# SSTuino_II.net
KiCad netlist of a schematic drawn in EAGLE
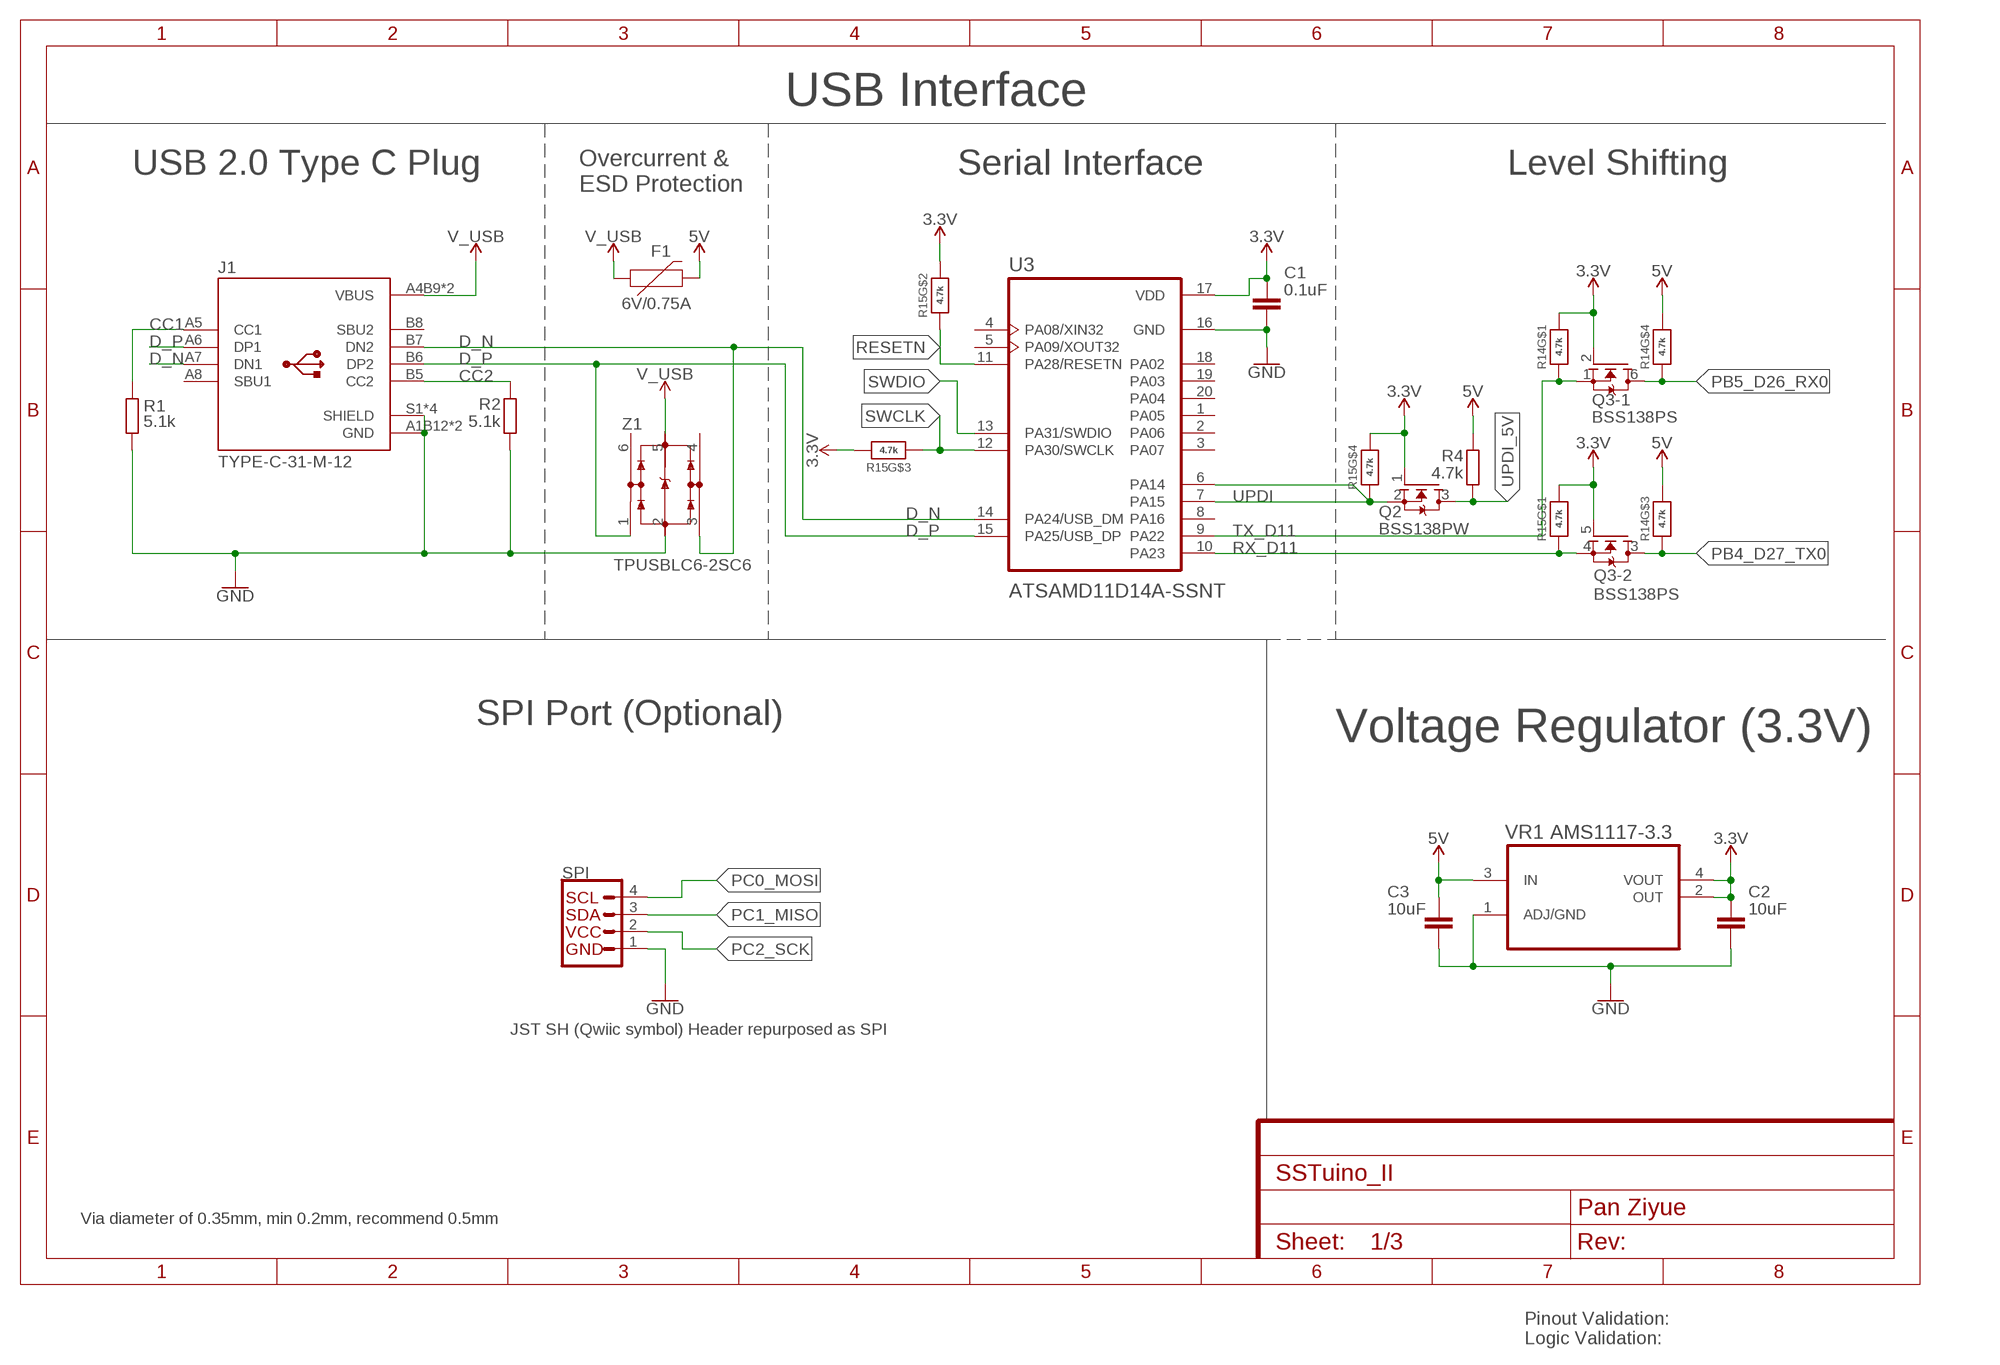
[diagram p0: schematic, sheet 1]
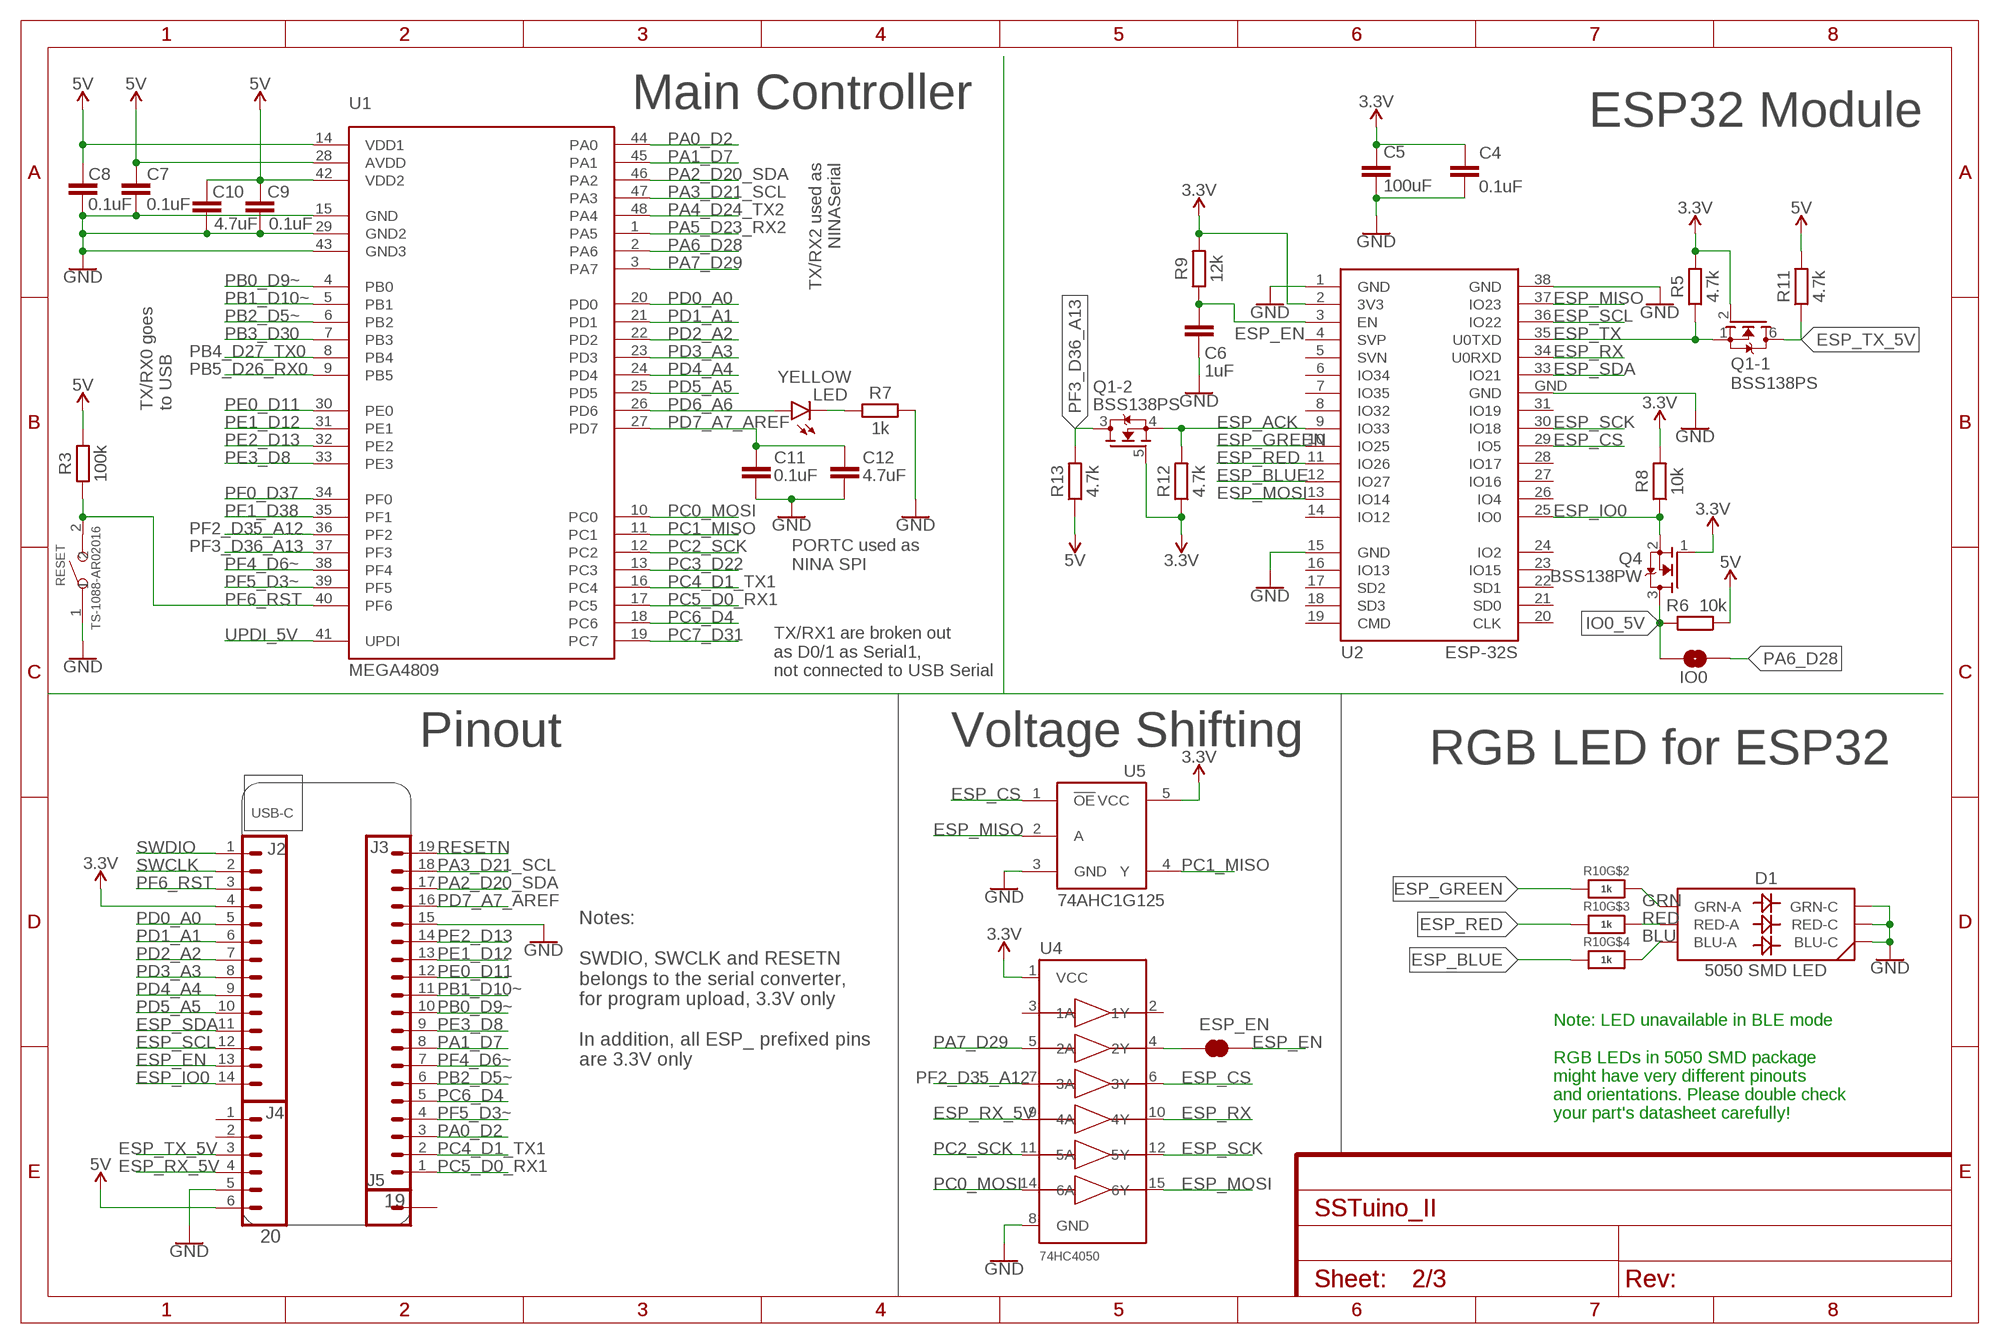
[diagram p1: schematic, sheet 2]
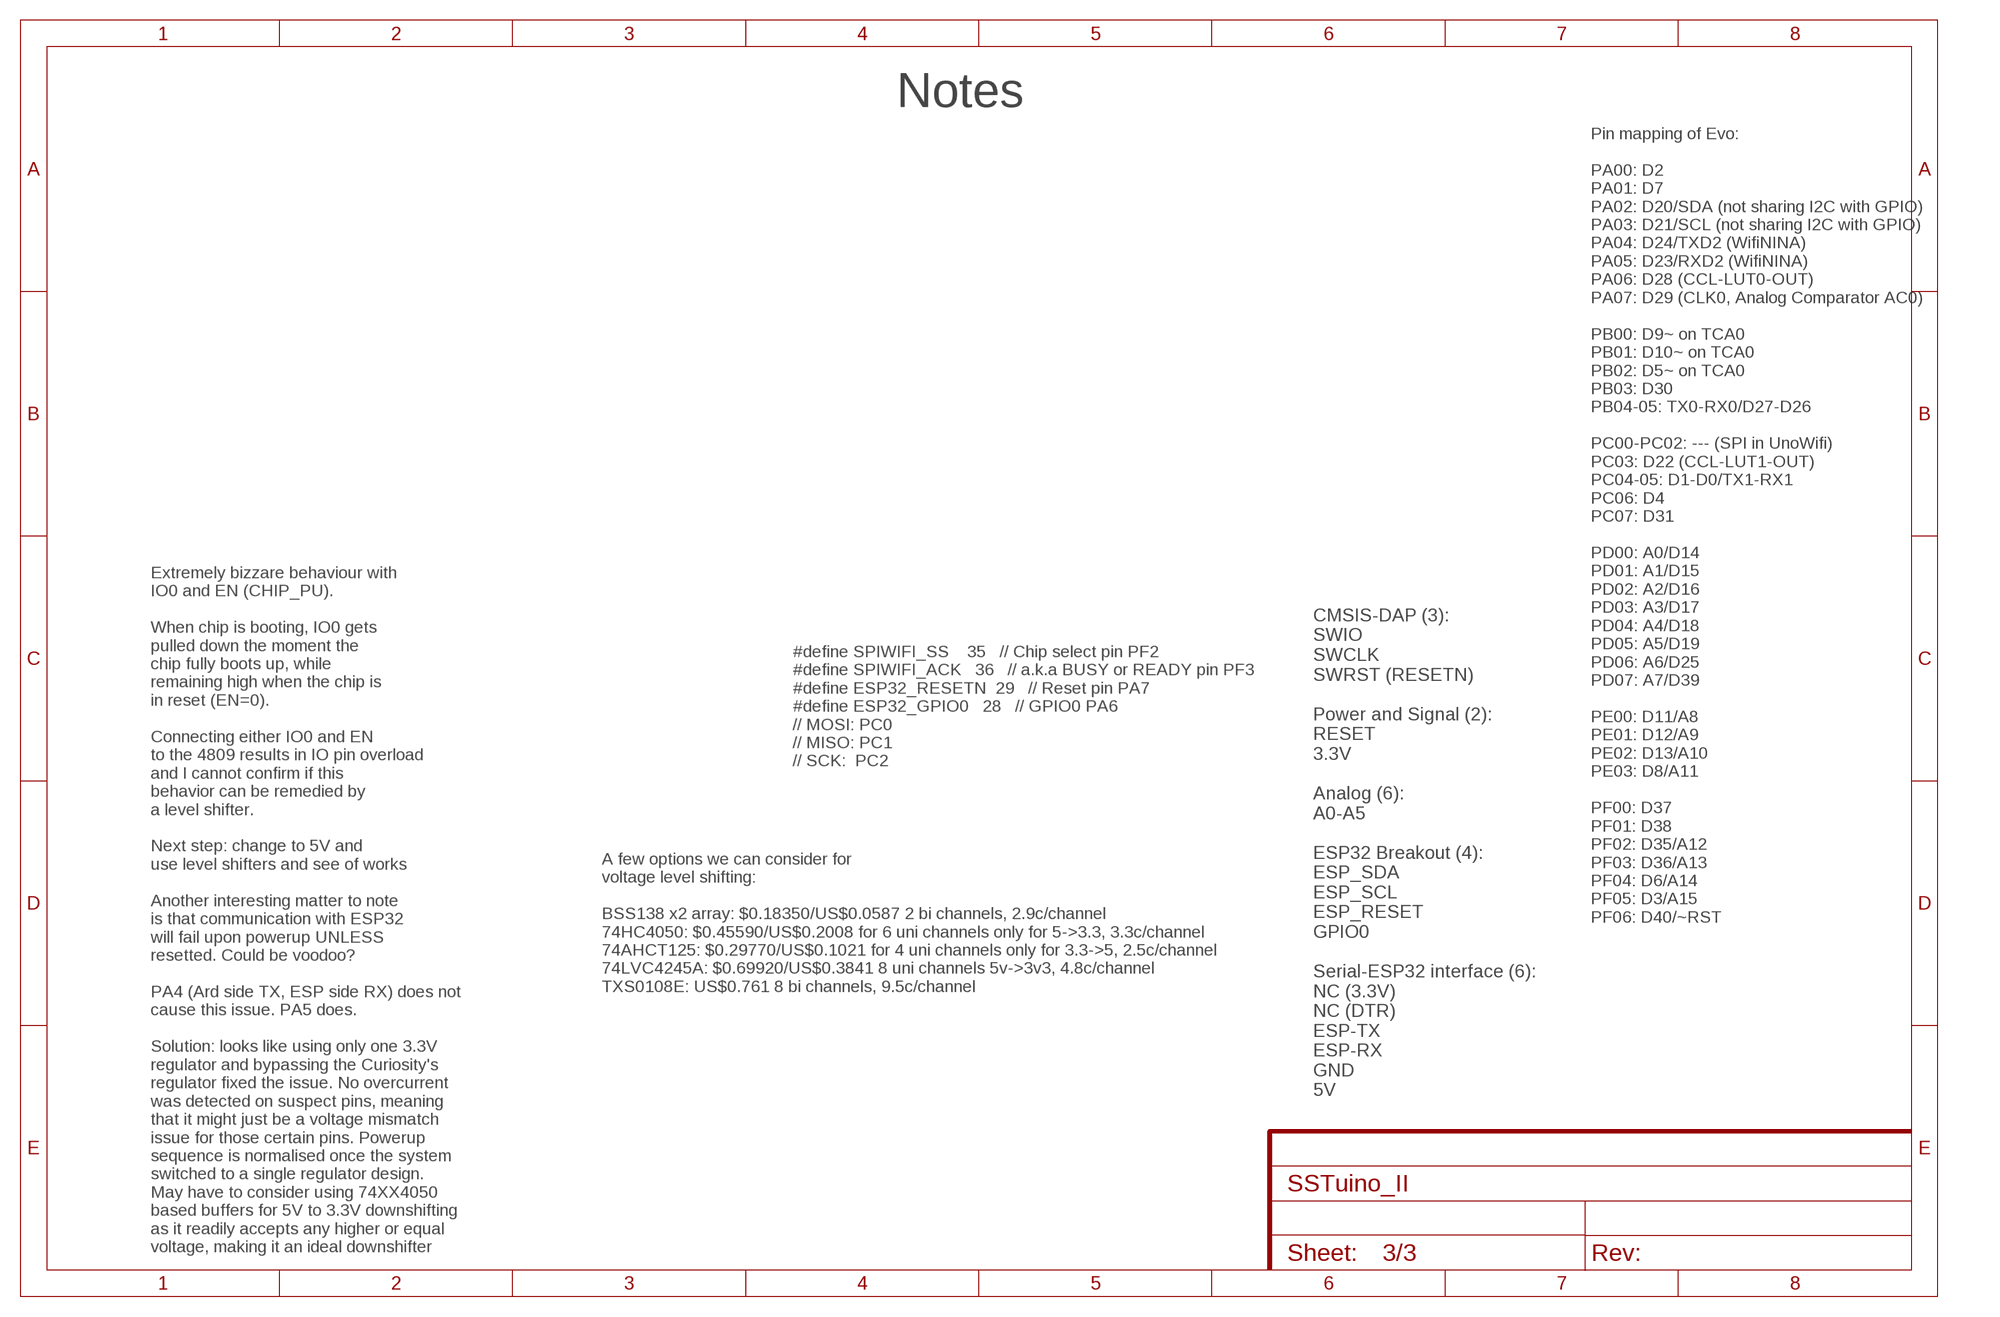
[diagram p2: schematic, sheet 3]

(export (version "E")
  (design (tool "Eeschema 10.0.6"))
  (components
    (comp (ref "C4")
      (value "0.1uF")
      (footprint "eagle-import:CAPC1005X60")
      (fields (field (name "LCSC_PART") "C1525"))
      (libsource (lib "eagle-import") (part "CCHIP-0402(1005-METRIC)_"))
    )
    (comp (ref "C5")
      (value "100uF")
      (footprint "eagle-import:CAPC3216X135")
      (fields (field (name "LCSC_PART") "C15008"))
      (libsource (lib "eagle-import") (part "CCHIP-1206(3216-METRIC)_"))
    )
    (comp (ref "C6")
      (value "1uF")
      (footprint "eagle-import:CAPC1005X60")
      (fields (field (name "LCSC_PART") "C52923"))
      (libsource (lib "eagle-import") (part "CCHIP-0402(1005-METRIC)_"))
    )
    (comp (ref "C7")
      (value "0.1uF")
      (footprint "eagle-import:CAPC1005X60")
      (libsource (lib "eagle-import") (part "CCHIP-0402(1005-METRIC)_"))
    )
    (comp (ref "C8")
      (value "0.1uF")
      (footprint "eagle-import:CAPC1005X60")
      (libsource (lib "eagle-import") (part "CCHIP-0402(1005-METRIC)_"))
    )
    (comp (ref "C9")
      (value "0.1uF")
      (footprint "eagle-import:CAPC1005X60")
      (libsource (lib "eagle-import") (part "CCHIP-0402(1005-METRIC)_"))
    )
    (comp (ref "C10")
      (value "4.7uF")
      (footprint "eagle-import:CAPC1005X60")
      (libsource (lib "eagle-import") (part "CCHIP-0402(1005-METRIC)_"))
    )
    (comp (ref "C11")
      (value "0.1uF")
      (footprint "eagle-import:CAPC1005X60")
      (fields (field (name "LCSC_PART") "C1525"))
      (libsource (lib "eagle-import") (part "CCHIP-0402(1005-METRIC)_"))
    )
    (comp (ref "C12")
      (value "4.7uF")
      (footprint "eagle-import:CAPC1005X60")
      (fields (field (name "LCSC_PART") "C23733"))
      (libsource (lib "eagle-import") (part "CCHIP-0402(1005-METRIC)_"))
    )
    (comp (ref "D1")
      (value "5050 SMD LED")
      (footprint "eagle-import:LED-TRICOLOR-5050")
      (fields (field (name "LCSC_PART") "C784540"))
      (libsource (lib "eagle-import") (part "LED-RGBTC5050RGBF08"))
    )
    (comp (ref "ESP_EN")
      (value "JUMPER-SMT_2_NC_TRACE_SILK")
      (footprint "eagle-import:SMT-JUMPER_2_NC_TRACE_SILK")
      (libsource (lib "eagle-import") (part "JUMPER-SMT_2_NC_TRACE_SILK"))
    )
    (comp (ref "IO0")
      (value "JUMPER-SMT_2_NO_SILK")
      (footprint "eagle-import:SMT-JUMPER_2_NO_SILK")
      (libsource (lib "eagle-import") (part "JUMPER-SMT_2_NO_SILK"))
    )
    (comp (ref "J2")
      (value "CONN_14NO_SILK")
      (footprint "eagle-import:1X14_NO_SILK")
      (libsource (lib "eagle-import") (part "CONN_14NO_SILK"))
    )
    (comp (ref "J3")
      (value "CONN_191X19_NO_SILK")
      (footprint "eagle-import:1X19_NO_SILK")
      (libsource (lib "eagle-import") (part "CONN_191X19_NO_SILK"))
    )
    (comp (ref "J4")
      (value "CONN_06NO_SILK_FEMALE_PTH")
      (footprint "eagle-import:1X06_NO_SILK")
      (libsource (lib "eagle-import") (part "CONN_06NO_SILK_FEMALE_PTH"))
    )
    (comp (ref "J5")
      (value "CONN_01PTH_NO_SILK_YES_STOP")
      (footprint "eagle-import:1X01_NO_SILK")
      (libsource (lib "eagle-import") (part "CONN_01PTH_NO_SILK_YES_STOP"))
    )
    (comp (ref "LED")
      (value "YELLOW")
      (footprint "eagle-import:LED-0603")
      (fields (field (name "LCSC_PART") "C72038"))
      (libsource (lib "eagle-import") (part "LED0603"))
    )
    (comp (ref "Q1")
      (value "BSS138PS")
      (footprint "eagle-import:ARDUINO-TRANSISTORS_SOT363")
      (fields (field (name "MANUFACTURER") "NXP") (field (name "LCSC_PART") "C193381"))
      (libsource (lib "eagle-import") (part "BSS138PS"))
    )
    (comp (ref "Q4")
      (value "BSS138PW")
      (footprint "eagle-import:SOT65P210X110-3N")
      (fields (field (name "MF") "NXP Semiconductors") (field (name "LCSC_PART") "C919583"))
      (libsource (lib "eagle-import") (part "BSS138PW"))
    )
    (comp (ref "R3")
      (value "100k")
      (footprint "eagle-import:RESC1005X40")
      (fields (field (name "LCSC_PART") "C25741"))
      (libsource (lib "eagle-import") (part "RCHIP-0402(1005-METRIC)_"))
    )
    (comp (ref "R5")
      (value "4.7k")
      (footprint "eagle-import:RESC1005X40")
      (fields (field (name "LCSC_PART") "C25900"))
      (libsource (lib "eagle-import") (part "RCHIP-0402(1005-METRIC)_"))
    )
    (comp (ref "R6")
      (value "10k")
      (footprint "eagle-import:RESC1005X40")
      (fields (field (name "LCSC_PART") "C25744"))
      (libsource (lib "eagle-import") (part "RCHIP-0402(1005-METRIC)_"))
    )
    (comp (ref "R7")
      (value "1k")
      (footprint "eagle-import:RESC1005X40")
      (fields (field (name "LCSC_PART") "C11702"))
      (libsource (lib "eagle-import") (part "RCHIP-0402(1005-METRIC)_"))
    )
    (comp (ref "R8")
      (value "10k")
      (footprint "eagle-import:RESC1005X40")
      (fields (field (name "LCSC_PART") "C25744"))
      (libsource (lib "eagle-import") (part "RCHIP-0402(1005-METRIC)_"))
    )
    (comp (ref "R9")
      (value "12k")
      (footprint "eagle-import:RESC1005X40")
      (fields (field (name "LCSC_PART") "C25752"))
      (libsource (lib "eagle-import") (part "RCHIP-0402(1005-METRIC)_"))
    )
    (comp (ref "R10")
      (value "1k")
      (footprint "eagle-import:RESPACK_4X0402")
      (fields (field (name "LCSC_PART") "C25726"))
      (libsource (lib "eagle-import") (part "RESISTOR_4PACK0402"))
    )
    (comp (ref "R11")
      (value "4.7k")
      (footprint "eagle-import:RESC1005X40")
      (fields (field (name "LCSC_PART") "C25900"))
      (libsource (lib "eagle-import") (part "RCHIP-0402(1005-METRIC)_"))
    )
    (comp (ref "R12")
      (value "4.7k")
      (footprint "eagle-import:RESC1005X40")
      (fields (field (name "LCSC_PART") "C25900"))
      (libsource (lib "eagle-import") (part "RCHIP-0402(1005-METRIC)_"))
    )
    (comp (ref "R13")
      (value "4.7k")
      (footprint "eagle-import:RESC1005X40")
      (fields (field (name "LCSC_PART") "C25900"))
      (libsource (lib "eagle-import") (part "RCHIP-0402(1005-METRIC)_"))
    )
    (comp (ref "RESET")
      (value "TS-1088-AR02016")
      (footprint "eagle-import:SW2-2.6-3.9X2.9X1.5+0.4MM")
      (fields
        (field (name "LCSC_PART") "C115357")
        (field (name "MPN") "SKRKAEE020")
        (field (name "LCSC_PART_1") "C720477")
      )
      (libsource (lib "eagle-import") (part "SMD-BUTTON(2P-3.9X2.9X1.5+0.4MM)-SKRKAEE020"))
    )
    (comp (ref "U1")
      (value "MEGA4809")
      (footprint "eagle-import:TQFP48")
      (fields (field (name "LCSC_PART") "C189475"))
      (libsource (lib "eagle-import") (part "MEGA4809"))
    )
    (comp (ref "U2")
      (value "ESP-32S")
      (footprint "eagle-import:ESP-32S")
      (fields (field (name "LCSC_PART") "C277944"))
      (libsource (lib "eagle-import") (part "ESP-32S"))
    )
    (comp (ref "U4")
      (value "74HC4050")
      (footprint "eagle-import:TSSOP16")
      (fields (field (name "LCSC_PART") "C352825"))
      (libsource (lib "eagle-import") (part "74HC4050DTSSOP"))
    )
    (comp (ref "U5")
      (value "74AHC1G125")
      (footprint "eagle-import:SOT23-5L")
      (fields (field (name "LCSC_PART") "C7468"))
      (libsource (lib "eagle-import") (part "74AHC1G125"))
    )
    (comp (ref "C1")
      (value "0.1uF")
      (footprint "eagle-import:CAPC1005X60")
      (fields (field (name "LCSC_PART") "C696352"))
      (libsource (lib "eagle-import") (part "CCHIP-0402(1005-METRIC)_"))
    )
    (comp (ref "C2")
      (value "10uF")
      (footprint "eagle-import:CAPC1608X85")
      (fields (field (name "LCSC_PART") "C19702"))
      (libsource (lib "eagle-import") (part "CCHIP-0603(1608-METRIC)_"))
    )
    (comp (ref "C3")
      (value "10uF")
      (footprint "eagle-import:CAPC1608X85")
      (fields (field (name "LCSC_PART") "C19702"))
      (libsource (lib "eagle-import") (part "CCHIP-0603(1608-METRIC)_"))
    )
    (comp (ref "F1")
      (value "6V/0.75A")
      (footprint "eagle-import:1206")
      (fields (field (name "LCSC_PART") "C99563"))
      (libsource (lib "eagle-import") (part "PPTC_THREE-QUARTER-AMP"))
    )
    (comp (ref "J1")
      (value "TYPE-C-31-M-12")
      (footprint "eagle-import:HRO_TYPE-C-31-M-12")
      (fields (field (name "MF") "HRO Electronics Co., Ltd.") (field (name "LCSC_PART") "C165948"))
      (libsource (lib "eagle-import") (part "TYPE-C-31-M-12"))
    )
    (comp (ref "Q2")
      (value "BSS138PW")
      (footprint "eagle-import:SOT65P210X110-3N")
      (fields (field (name "MF") "NXP Semiconductors") (field (name "LCSC_PART") "C193366"))
      (libsource (lib "eagle-import") (part "BSS138PW"))
    )
    (comp (ref "Q3")
      (value "BSS138PS")
      (footprint "eagle-import:ARDUINO-TRANSISTORS_SOT363")
      (fields (field (name "MANUFACTURER") "NXP") (field (name "LCSC_PART") "C193381"))
      (libsource (lib "eagle-import") (part "BSS138PS"))
    )
    (comp (ref "R1")
      (value "5.1k")
      (footprint "eagle-import:RESC1005X40")
      (fields (field (name "LCSC_PART") "C25905"))
      (libsource (lib "eagle-import") (part "RCHIP-0402(1005-METRIC)_"))
    )
    (comp (ref "R2")
      (value "5.1k")
      (footprint "eagle-import:RESC1005X40")
      (fields (field (name "LCSC_PART") "C25905"))
      (libsource (lib "eagle-import") (part "RCHIP-0402(1005-METRIC)_"))
    )
    (comp (ref "R4")
      (value "4.7k")
      (footprint "eagle-import:RESC1005X40")
      (fields (field (name "LCSC_PART") "C25900"))
      (libsource (lib "eagle-import") (part "RCHIP-0402(1005-METRIC)_"))
    )
    (comp (ref "R14")
      (value "4.7k")
      (footprint "eagle-import:RESPACK_4X0402")
      (fields (field (name "LCSC_PART") "C29586"))
      (libsource (lib "eagle-import") (part "RESISTOR_4PACK0402"))
    )
    (comp (ref "R15")
      (value "4.7k")
      (footprint "eagle-import:RESPACK_4X0402")
      (fields (field (name "LCSC_PART") "C29586"))
      (libsource (lib "eagle-import") (part "RESISTOR_4PACK0402"))
    )
    (comp (ref "SPI")
      (value "QWIIC_CONNECTORJS-1MM")
      (footprint "eagle-import:1X04_1MM_RA")
      (libsource (lib "eagle-import") (part "QWIIC_CONNECTORJS-1MM"))
    )
    (comp (ref "U3")
      (value "ATSAMD11D14A-SSNT")
      (footprint "eagle-import:SOIC127P1030X265-20N")
      (fields (field (name "MF") "Microchip") (field (name "LCSC_PART") "C2053599"))
      (libsource (lib "eagle-import") (part "ATSAMD11D14A-SSNT"))
    )
    (comp (ref "VR1")
      (value "AMS1117-3.3")
      (footprint "eagle-import:SOT230P696X180-4N")
      (fields (field (name "MPN") "LM1117MP-3.3") (field (name "LCSC_PART") "C6186"))
      (libsource (lib "eagle-import") (part "LM1117MP-3.3"))
    )
    (comp (ref "Z1")
      (value "TPUSBLC6-2SC6")
      (footprint "eagle-import:SOT95P280X110-6N")
      (fields (field (name "LCSC_PART") "C558442"))
      (libsource (lib "eagle-import") (part "TPUSBLC6-2SC6"))
    )
  )
  (nets
    (net (code "1") (name "3.3V") (class "Default")
      (node (ref "C1") (pin "1") (pinfunction "1_1") (pintype "passive"))
      (node (ref "C2") (pin "1") (pinfunction "1_1") (pintype "passive"))
      (node (ref "C4") (pin "1") (pinfunction "1_1") (pintype "passive"))
      (node (ref "C5") (pin "1") (pinfunction "1_1") (pintype "passive"))
      (node (ref "J2") (pin "4") (pinfunction "4_4") (pintype "passive"))
      (node (ref "Q1") (pin "2") (pinfunction "G_2") (pintype "passive"))
      (node (ref "Q1") (pin "5") (pinfunction "G_5") (pintype "passive"))
      (node (ref "Q2") (pin "1") (pinfunction "G_1") (pintype "passive"))
      (node (ref "Q3") (pin "2") (pinfunction "G_2") (pintype "passive"))
      (node (ref "Q3") (pin "5") (pinfunction "G_5") (pintype "passive"))
      (node (ref "Q4") (pin "1") (pinfunction "G_1") (pintype "passive"))
      (node (ref "R12") (pin "1") (pinfunction "1_1") (pintype "passive"))
      (node (ref "R14") (pin "8") (pinfunction "2_8") (pintype "passive"))
      (node (ref "R15") (pin "5") (pinfunction "2_5") (pintype "passive"))
      (node (ref "R15") (pin "6") (pinfunction "2_6") (pintype "passive"))
      (node (ref "R15") (pin "7") (pinfunction "2_7") (pintype "passive"))
      (node (ref "R15") (pin "8") (pinfunction "2_8") (pintype "passive"))
      (node (ref "R5") (pin "2") (pinfunction "2_2") (pintype "passive"))
      (node (ref "R8") (pin "2") (pinfunction "2_2") (pintype "passive"))
      (node (ref "R9") (pin "2") (pinfunction "2_2") (pintype "passive"))
      (node (ref "U2") (pin "2") (pinfunction "3V3_2") (pintype "power_in"))
      (node (ref "U3") (pin "17") (pinfunction "VDD_17") (pintype "power_in"))
      (node (ref "U4") (pin "1") (pinfunction "VCC_1") (pintype "bidirectional"))
      (node (ref "U5") (pin "5") (pinfunction "VCC_5") (pintype "power_in"))
      (node (ref "VR1") (pin "2") (pinfunction "OUT_2") (pintype "output"))
      (node (ref "VR1") (pin "4") (pinfunction "VOUT_4") (pintype "output"))
    )
    (net (code "2") (name "5V") (class "Default")
      (node (ref "C10") (pin "1") (pinfunction "1_1") (pintype "passive"))
      (node (ref "C3") (pin "1") (pinfunction "1_1") (pintype "passive"))
      (node (ref "C7") (pin "1") (pinfunction "1_1") (pintype "passive"))
      (node (ref "C8") (pin "1") (pinfunction "1_1") (pintype "passive"))
      (node (ref "C9") (pin "1") (pinfunction "1_1") (pintype "passive"))
      (node (ref "F1") (pin "2") (pinfunction "2_2") (pintype "bidirectional"))
      (node (ref "J4") (pin "6") (pinfunction "6_6") (pintype "passive"))
      (node (ref "R11") (pin "2") (pinfunction "2_2") (pintype "passive"))
      (node (ref "R13") (pin "1") (pinfunction "1_1") (pintype "passive"))
      (node (ref "R14") (pin "5") (pinfunction "2_5") (pintype "passive"))
      (node (ref "R14") (pin "6") (pinfunction "2_6") (pintype "passive"))
      (node (ref "R3") (pin "2") (pinfunction "2_2") (pintype "passive"))
      (node (ref "R4") (pin "2") (pinfunction "2_2") (pintype "passive"))
      (node (ref "R6") (pin "1") (pinfunction "1_1") (pintype "passive"))
      (node (ref "U1") (pin "14") (pinfunction "VDD1_14") (pintype "bidirectional"))
      (node (ref "U1") (pin "28") (pinfunction "AVDD_28") (pintype "bidirectional"))
      (node (ref "U1") (pin "42") (pinfunction "VDD2_42") (pintype "bidirectional"))
      (node (ref "VR1") (pin "3") (pinfunction "IN_3") (pintype "input"))
    )
    (net (code "3") (name "BLU") (class "Default")
      (node (ref "D1") (pin "6") (pinfunction "BLU-A_6") (pintype "bidirectional"))
      (node (ref "R10") (pin "5") (pinfunction "2_5") (pintype "passive"))
    )
    (net (code "4") (name "CC1") (class "Default")
      (node (ref "J1") (pin "A5") (pinfunction "CC1_A5") (pintype "bidirectional"))
      (node (ref "R1") (pin "1") (pinfunction "1_1") (pintype "passive"))
    )
    (net (code "5") (name "CC2") (class "Default")
      (node (ref "J1") (pin "B5") (pinfunction "CC2_B5") (pintype "bidirectional"))
      (node (ref "R2") (pin "2") (pinfunction "2_2") (pintype "passive"))
    )
    (net (code "6") (name "D_N") (class "Default")
      (node (ref "J1") (pin "A7") (pinfunction "DN1_A7") (pintype "bidirectional"))
      (node (ref "J1") (pin "B7") (pinfunction "DN2_B7") (pintype "bidirectional"))
      (node (ref "U3") (pin "14") (pinfunction "PA24/USB_DM_14") (pintype "bidirectional"))
      (node (ref "Z1") (pin "3") (pinfunction "IO2_3") (pintype "passive"))
    )
    (net (code "7") (name "D_P") (class "Default")
      (node (ref "J1") (pin "A6") (pinfunction "DP1_A6") (pintype "bidirectional"))
      (node (ref "J1") (pin "B6") (pinfunction "DP2_B6") (pintype "bidirectional"))
      (node (ref "U3") (pin "15") (pinfunction "PA25/USB_DP_15") (pintype "bidirectional"))
      (node (ref "Z1") (pin "1") (pinfunction "IO1_1") (pintype "passive"))
    )
    (net (code "8") (name "ESP_ACK") (class "Default")
      (node (ref "Q1") (pin "4") (pinfunction "S_4") (pintype "passive"))
      (node (ref "R12") (pin "2") (pinfunction "2_2") (pintype "passive"))
      (node (ref "U2") (pin "9") (pinfunction "IO33_9") (pintype "bidirectional"))
    )
    (net (code "9") (name "ESP_BLUE") (class "Default")
      (node (ref "R10") (pin "4") (pinfunction "1_4") (pintype "passive"))
      (node (ref "U2") (pin "12") (pinfunction "IO27_12") (pintype "bidirectional"))
    )
    (net (code "10") (name "ESP_CS") (class "Default")
      (node (ref "U2") (pin "29") (pinfunction "IO5_29") (pintype "bidirectional"))
      (node (ref "U4") (pin "6") (pinfunction "3Y_6") (pintype "bidirectional"))
      (node (ref "U5") (pin "1") (pinfunction "~{OE}_1") (pintype "input"))
    )
    (net (code "11") (name "ESP_EN") (class "Default")
      (node (ref "C6") (pin "2") (pinfunction "2_2") (pintype "passive"))
      (node (ref "ESP_EN") (pin "2") (pinfunction "2_2") (pintype "passive"))
      (node (ref "J2") (pin "13") (pinfunction "13_13") (pintype "passive"))
      (node (ref "R9") (pin "1") (pinfunction "1_1") (pintype "passive"))
      (node (ref "U2") (pin "3") (pinfunction "EN_3") (pintype "input"))
    )
    (net (code "12") (name "ESP_GREEN") (class "Default")
      (node (ref "R10") (pin "2") (pinfunction "1_2") (pintype "passive"))
      (node (ref "U2") (pin "10") (pinfunction "IO25_10") (pintype "bidirectional"))
    )
    (net (code "13") (name "ESP_IO0") (class "Default")
      (node (ref "J2") (pin "14") (pinfunction "14_14") (pintype "passive"))
      (node (ref "Q4") (pin "2") (pinfunction "S_2") (pintype "passive"))
      (node (ref "R8") (pin "1") (pinfunction "1_1") (pintype "passive"))
      (node (ref "U2") (pin "25") (pinfunction "IO0_25") (pintype "bidirectional"))
    )
    (net (code "14") (name "ESP_MISO") (class "Default")
      (node (ref "U2") (pin "37") (pinfunction "IO23_37") (pintype "bidirectional"))
      (node (ref "U5") (pin "2") (pinfunction "A_2") (pintype "input"))
    )
    (net (code "15") (name "ESP_MOSI") (class "Default")
      (node (ref "U2") (pin "13") (pinfunction "IO14_13") (pintype "bidirectional"))
      (node (ref "U4") (pin "15") (pinfunction "6Y_15") (pintype "bidirectional"))
    )
    (net (code "16") (name "ESP_RED") (class "Default")
      (node (ref "R10") (pin "3") (pinfunction "1_3") (pintype "passive"))
      (node (ref "U2") (pin "11") (pinfunction "IO26_11") (pintype "bidirectional"))
    )
    (net (code "17") (name "ESP_RX") (class "Default")
      (node (ref "U2") (pin "34") (pinfunction "U0RXD_34") (pintype "bidirectional"))
      (node (ref "U4") (pin "10") (pinfunction "4Y_10") (pintype "bidirectional"))
    )
    (net (code "18") (name "ESP_RX_5V") (class "Default")
      (node (ref "J4") (pin "4") (pinfunction "4_4") (pintype "passive"))
      (node (ref "U4") (pin "9") (pinfunction "4A_9") (pintype "bidirectional"))
    )
    (net (code "19") (name "ESP_SCK") (class "Default")
      (node (ref "U2") (pin "30") (pinfunction "IO18_30") (pintype "bidirectional"))
      (node (ref "U4") (pin "12") (pinfunction "5Y_12") (pintype "bidirectional"))
    )
    (net (code "20") (name "ESP_SCL") (class "Default")
      (node (ref "J2") (pin "12") (pinfunction "12_12") (pintype "passive"))
      (node (ref "U2") (pin "36") (pinfunction "IO22_36") (pintype "bidirectional"))
    )
    (net (code "21") (name "ESP_SDA") (class "Default")
      (node (ref "J2") (pin "11") (pinfunction "11_11") (pintype "passive"))
      (node (ref "U2") (pin "33") (pinfunction "IO21_33") (pintype "bidirectional"))
    )
    (net (code "22") (name "ESP_TX") (class "Default")
      (node (ref "Q1") (pin "1") (pinfunction "S_1") (pintype "passive"))
      (node (ref "R5") (pin "1") (pinfunction "1_1") (pintype "passive"))
      (node (ref "U2") (pin "35") (pinfunction "U0TXD_35") (pintype "bidirectional"))
    )
    (net (code "23") (name "ESP_TX_5V") (class "Default")
      (node (ref "J4") (pin "3") (pinfunction "3_3") (pintype "passive"))
      (node (ref "Q1") (pin "6") (pinfunction "D_6") (pintype "passive"))
      (node (ref "R11") (pin "1") (pinfunction "1_1") (pintype "passive"))
    )
    (net (code "24") (name "GND") (class "Default")
      (node (ref "C1") (pin "2") (pinfunction "2_2") (pintype "passive"))
      (node (ref "C10") (pin "2") (pinfunction "2_2") (pintype "passive"))
      (node (ref "C11") (pin "2") (pinfunction "2_2") (pintype "passive"))
      (node (ref "C12") (pin "2") (pinfunction "2_2") (pintype "passive"))
      (node (ref "C2") (pin "2") (pinfunction "2_2") (pintype "passive"))
      (node (ref "C3") (pin "2") (pinfunction "2_2") (pintype "passive"))
      (node (ref "C4") (pin "2") (pinfunction "2_2") (pintype "passive"))
      (node (ref "C5") (pin "2") (pinfunction "2_2") (pintype "passive"))
      (node (ref "C6") (pin "1") (pinfunction "1_1") (pintype "passive"))
      (node (ref "C7") (pin "2") (pinfunction "2_2") (pintype "passive"))
      (node (ref "C8") (pin "2") (pinfunction "2_2") (pintype "passive"))
      (node (ref "C9") (pin "2") (pinfunction "2_2") (pintype "passive"))
      (node (ref "D1") (pin "1") (pinfunction "BLU-C_1") (pintype "bidirectional"))
      (node (ref "D1") (pin "2") (pinfunction "RED-C_2") (pintype "bidirectional"))
      (node (ref "D1") (pin "3") (pinfunction "GRN-C_3") (pintype "bidirectional"))
      (node (ref "J1") (pin "A1B12") (pinfunction "GND_A1B12") (pintype "power_in"))
      (node (ref "J1") (pin "B1A12") (pinfunction "GND_B1A12") (pintype "power_in"))
      (node (ref "J1") (pin "S1") (pinfunction "SHIELD_S1") (pintype "passive"))
      (node (ref "J1") (pin "S2") (pinfunction "SHIELD_S2") (pintype "passive"))
      (node (ref "J1") (pin "S3") (pinfunction "SHIELD_S3") (pintype "passive"))
      (node (ref "J1") (pin "S4") (pinfunction "SHIELD_S4") (pintype "passive"))
      (node (ref "J3") (pin "15") (pinfunction "15_15") (pintype "passive"))
      (node (ref "J4") (pin "5") (pinfunction "5_5") (pintype "passive"))
      (node (ref "R1") (pin "2") (pinfunction "2_2") (pintype "passive"))
      (node (ref "R2") (pin "1") (pinfunction "1_1") (pintype "passive"))
      (node (ref "R7") (pin "2") (pinfunction "2_2") (pintype "passive"))
      (node (ref "RESET") (pin "1") (pinfunction "1_1") (pintype "bidirectional"))
      (node (ref "SPI") (pin "1") (pinfunction "GND_1") (pintype "power_in"))
      (node (ref "U1") (pin "15") (pinfunction "GND_15") (pintype "bidirectional"))
      (node (ref "U1") (pin "29") (pinfunction "GND2_29") (pintype "bidirectional"))
      (node (ref "U1") (pin "43") (pinfunction "GND3_43") (pintype "bidirectional"))
      (node (ref "U2") (pin "1") (pinfunction "GND_1") (pintype "power_in"))
      (node (ref "U2") (pin "15") (pinfunction "GND_15") (pintype "power_in"))
      (node (ref "U2") (pin "38") (pinfunction "GND_38") (pintype "power_in"))
      (node (ref "U2") (pin "GND") (pinfunction "GND_GND") (pintype "power_in"))
      (node (ref "U3") (pin "16") (pinfunction "GND_16") (pintype "power_in"))
      (node (ref "U4") (pin "8") (pinfunction "GND_8") (pintype "bidirectional"))
      (node (ref "U5") (pin "3") (pinfunction "GND_3") (pintype "power_in"))
      (node (ref "VR1") (pin "1") (pinfunction "ADJ/GND_1") (pintype "passive"))
      (node (ref "Z1") (pin "2") (pinfunction "VSS_2") (pintype "power_in"))
    )
    (net (code "25") (name "GRN") (class "Default")
      (node (ref "D1") (pin "4") (pinfunction "GRN-A_4") (pintype "bidirectional"))
      (node (ref "R10") (pin "7") (pinfunction "2_7") (pintype "passive"))
    )
    (net (code "26") (name "IO0_5V") (class "Default")
      (node (ref "IO0") (pin "2") (pinfunction "2_2") (pintype "passive"))
      (node (ref "Q4") (pin "3") (pinfunction "D_3") (pintype "passive"))
      (node (ref "R6") (pin "2") (pinfunction "2_2") (pintype "passive"))
    )
    (net (code "27") (name "Net-(LED-PadC)") (class "Default")
      (node (ref "LED") (pin "C") (pinfunction "C_C") (pintype "passive"))
      (node (ref "R7") (pin "1") (pinfunction "1_1") (pintype "passive"))
    )
    (net (code "28") (name "Net-(U4-2Y)") (class "Default")
      (node (ref "ESP_EN") (pin "1") (pinfunction "1_1") (pintype "passive"))
      (node (ref "U4") (pin "4") (pinfunction "2Y_4") (pintype "bidirectional"))
    )
    (net (code "29") (name "PA0_D2") (class "Default")
      (node (ref "J3") (pin "3") (pinfunction "3_3") (pintype "passive"))
      (node (ref "U1") (pin "44") (pinfunction "PA0_44") (pintype "bidirectional"))
    )
    (net (code "30") (name "PA1_D7") (class "Default")
      (node (ref "J3") (pin "8") (pinfunction "8_8") (pintype "passive"))
      (node (ref "U1") (pin "45") (pinfunction "PA1_45") (pintype "bidirectional"))
    )
    (net (code "31") (name "PA2_D20_SDA") (class "Default")
      (node (ref "J3") (pin "17") (pinfunction "17_17") (pintype "passive"))
      (node (ref "U1") (pin "46") (pinfunction "PA2_46") (pintype "bidirectional"))
    )
    (net (code "32") (name "PA3_D21_SCL") (class "Default")
      (node (ref "J3") (pin "18") (pinfunction "18_18") (pintype "passive"))
      (node (ref "U1") (pin "47") (pinfunction "PA3_47") (pintype "bidirectional"))
    )
    (net (code "33") (name "PA4_D24_TX2") (class "Default")
      (node (ref "U1") (pin "48") (pinfunction "PA4_48") (pintype "bidirectional"))
    )
    (net (code "34") (name "PA5_D23_RX2") (class "Default")
      (node (ref "U1") (pin "1") (pinfunction "PA5_1") (pintype "bidirectional"))
    )
    (net (code "35") (name "PA6_D28") (class "Default")
      (node (ref "IO0") (pin "1") (pinfunction "1_1") (pintype "passive"))
      (node (ref "U1") (pin "2") (pinfunction "PA6_2") (pintype "bidirectional"))
    )
    (net (code "36") (name "PA7_D29") (class "Default")
      (node (ref "U1") (pin "3") (pinfunction "PA7_3") (pintype "bidirectional"))
      (node (ref "U4") (pin "5") (pinfunction "2A_5") (pintype "bidirectional"))
    )
    (net (code "37") (name "PB0_D9~{}") (class "Default")
      (node (ref "J3") (pin "10") (pinfunction "10_10") (pintype "passive"))
      (node (ref "U1") (pin "4") (pinfunction "PB0_4") (pintype "bidirectional"))
    )
    (net (code "38") (name "PB1_D10~{}") (class "Default")
      (node (ref "J3") (pin "11") (pinfunction "11_11") (pintype "passive"))
      (node (ref "U1") (pin "5") (pinfunction "PB1_5") (pintype "bidirectional"))
    )
    (net (code "39") (name "PB2_D5~{}") (class "Default")
      (node (ref "J3") (pin "6") (pinfunction "6_6") (pintype "passive"))
      (node (ref "U1") (pin "6") (pinfunction "PB2_6") (pintype "bidirectional"))
    )
    (net (code "40") (name "PB3_D30") (class "Default")
      (node (ref "U1") (pin "7") (pinfunction "PB3_7") (pintype "bidirectional"))
    )
    (net (code "41") (name "PB4_D27_TX0") (class "Default")
      (node (ref "Q3") (pin "3") (pinfunction "D_3") (pintype "passive"))
      (node (ref "R14") (pin "3") (pinfunction "1_3") (pintype "passive"))
      (node (ref "U1") (pin "8") (pinfunction "PB4_8") (pintype "bidirectional"))
    )
    (net (code "42") (name "PB5_D26_RX0") (class "Default")
      (node (ref "Q3") (pin "6") (pinfunction "D_6") (pintype "passive"))
      (node (ref "R14") (pin "4") (pinfunction "1_4") (pintype "passive"))
      (node (ref "U1") (pin "9") (pinfunction "PB5_9") (pintype "bidirectional"))
    )
    (net (code "43") (name "PC0_MOSI") (class "Default")
      (node (ref "SPI") (pin "4") (pinfunction "SCL_4") (pintype "passive"))
      (node (ref "U1") (pin "10") (pinfunction "PC0_10") (pintype "bidirectional"))
      (node (ref "U4") (pin "14") (pinfunction "6A_14") (pintype "bidirectional"))
    )
    (net (code "44") (name "PC1_MISO") (class "Default")
      (node (ref "SPI") (pin "3") (pinfunction "SDA_3") (pintype "passive"))
      (node (ref "U1") (pin "11") (pinfunction "PC1_11") (pintype "bidirectional"))
      (node (ref "U5") (pin "4") (pinfunction "Y_4") (pintype "output"))
    )
    (net (code "45") (name "PC2_SCK") (class "Default")
      (node (ref "SPI") (pin "2") (pinfunction "VCC_2") (pintype "power_in"))
      (node (ref "U1") (pin "12") (pinfunction "PC2_12") (pintype "bidirectional"))
      (node (ref "U4") (pin "11") (pinfunction "5A_11") (pintype "bidirectional"))
    )
    (net (code "46") (name "PC3_D22") (class "Default")
      (node (ref "U1") (pin "13") (pinfunction "PC3_13") (pintype "bidirectional"))
    )
    (net (code "47") (name "PC4_D1_TX1") (class "Default")
      (node (ref "J3") (pin "2") (pinfunction "2_2") (pintype "passive"))
      (node (ref "U1") (pin "16") (pinfunction "PC4_16") (pintype "bidirectional"))
    )
    (net (code "48") (name "PC5_D0_RX1") (class "Default")
      (node (ref "J3") (pin "1") (pinfunction "1_1") (pintype "passive"))
      (node (ref "U1") (pin "17") (pinfunction "PC5_17") (pintype "bidirectional"))
    )
    (net (code "49") (name "PC6_D4") (class "Default")
      (node (ref "J3") (pin "5") (pinfunction "5_5") (pintype "passive"))
      (node (ref "U1") (pin "18") (pinfunction "PC6_18") (pintype "bidirectional"))
    )
    (net (code "50") (name "PC7_D31") (class "Default")
      (node (ref "U1") (pin "19") (pinfunction "PC7_19") (pintype "bidirectional"))
    )
    (net (code "51") (name "PD0_A0") (class "Default")
      (node (ref "J2") (pin "5") (pinfunction "5_5") (pintype "passive"))
      (node (ref "U1") (pin "20") (pinfunction "PD0_20") (pintype "bidirectional"))
    )
    (net (code "52") (name "PD1_A1") (class "Default")
      (node (ref "J2") (pin "6") (pinfunction "6_6") (pintype "passive"))
      (node (ref "U1") (pin "21") (pinfunction "PD1_21") (pintype "bidirectional"))
    )
    (net (code "53") (name "PD2_A2") (class "Default")
      (node (ref "J2") (pin "7") (pinfunction "7_7") (pintype "passive"))
      (node (ref "U1") (pin "22") (pinfunction "PD2_22") (pintype "bidirectional"))
    )
    (net (code "54") (name "PD3_A3") (class "Default")
      (node (ref "J2") (pin "8") (pinfunction "8_8") (pintype "passive"))
      (node (ref "U1") (pin "23") (pinfunction "PD3_23") (pintype "bidirectional"))
    )
    (net (code "55") (name "PD4_A4") (class "Default")
      (node (ref "J2") (pin "9") (pinfunction "9_9") (pintype "passive"))
      (node (ref "U1") (pin "24") (pinfunction "PD4_24") (pintype "bidirectional"))
    )
    (net (code "56") (name "PD5_A5") (class "Default")
      (node (ref "J2") (pin "10") (pinfunction "10_10") (pintype "passive"))
      (node (ref "U1") (pin "25") (pinfunction "PD5_25") (pintype "bidirectional"))
    )
    (net (code "57") (name "PD6_A6") (class "Default")
      (node (ref "LED") (pin "A") (pinfunction "A_A") (pintype "passive"))
      (node (ref "U1") (pin "26") (pinfunction "PD6_26") (pintype "bidirectional"))
    )
    (net (code "58") (name "PD7_A7_AREF") (class "Default")
      (node (ref "C11") (pin "1") (pinfunction "1_1") (pintype "passive"))
      (node (ref "C12") (pin "1") (pinfunction "1_1") (pintype "passive"))
      (node (ref "J3") (pin "16") (pinfunction "16_16") (pintype "passive"))
      (node (ref "U1") (pin "27") (pinfunction "PD7_27") (pintype "bidirectional"))
    )
    (net (code "59") (name "PE0_D11") (class "Default")
      (node (ref "J3") (pin "12") (pinfunction "12_12") (pintype "passive"))
      (node (ref "U1") (pin "30") (pinfunction "PE0_30") (pintype "bidirectional"))
    )
    (net (code "60") (name "PE1_D12") (class "Default")
      (node (ref "J3") (pin "13") (pinfunction "13_13") (pintype "passive"))
      (node (ref "U1") (pin "31") (pinfunction "PE1_31") (pintype "bidirectional"))
    )
    (net (code "61") (name "PE2_D13") (class "Default")
      (node (ref "J3") (pin "14") (pinfunction "14_14") (pintype "passive"))
      (node (ref "U1") (pin "32") (pinfunction "PE2_32") (pintype "bidirectional"))
    )
    (net (code "62") (name "PE3_D8") (class "Default")
      (node (ref "J3") (pin "9") (pinfunction "9_9") (pintype "passive"))
      (node (ref "U1") (pin "33") (pinfunction "PE3_33") (pintype "bidirectional"))
    )
    (net (code "63") (name "PF0_D37") (class "Default")
      (node (ref "U1") (pin "34") (pinfunction "PF0_34") (pintype "bidirectional"))
    )
    (net (code "64") (name "PF1_D38") (class "Default")
      (node (ref "U1") (pin "35") (pinfunction "PF1_35") (pintype "bidirectional"))
    )
    (net (code "65") (name "PF2_D35_A12") (class "Default")
      (node (ref "U1") (pin "36") (pinfunction "PF2_36") (pintype "bidirectional"))
      (node (ref "U4") (pin "7") (pinfunction "3A_7") (pintype "bidirectional"))
    )
    (net (code "66") (name "PF3_D36_A13") (class "Default")
      (node (ref "Q1") (pin "3") (pinfunction "D_3") (pintype "passive"))
      (node (ref "R13") (pin "2") (pinfunction "2_2") (pintype "passive"))
      (node (ref "U1") (pin "37") (pinfunction "PF3_37") (pintype "bidirectional"))
    )
    (net (code "67") (name "PF4_D6~{}") (class "Default")
      (node (ref "J3") (pin "7") (pinfunction "7_7") (pintype "passive"))
      (node (ref "U1") (pin "38") (pinfunction "PF4_38") (pintype "bidirectional"))
    )
    (net (code "68") (name "PF5_D3~{}") (class "Default")
      (node (ref "J3") (pin "4") (pinfunction "4_4") (pintype "passive"))
      (node (ref "U1") (pin "39") (pinfunction "PF5_39") (pintype "bidirectional"))
    )
    (net (code "69") (name "PF6_RST") (class "Default")
      (node (ref "J2") (pin "3") (pinfunction "3_3") (pintype "passive"))
      (node (ref "R3") (pin "1") (pinfunction "1_1") (pintype "passive"))
      (node (ref "RESET") (pin "2") (pinfunction "2_2") (pintype "bidirectional"))
      (node (ref "U1") (pin "40") (pinfunction "PF6_40") (pintype "bidirectional"))
    )
    (net (code "70") (name "RED") (class "Default")
      (node (ref "D1") (pin "5") (pinfunction "RED-A_5") (pintype "bidirectional"))
      (node (ref "R10") (pin "6") (pinfunction "2_6") (pintype "passive"))
    )
    (net (code "71") (name "RESETN") (class "Default")
      (node (ref "J3") (pin "19") (pinfunction "19_19") (pintype "passive"))
      (node (ref "R15") (pin "2") (pinfunction "1_2") (pintype "passive"))
      (node (ref "U3") (pin "11") (pinfunction "PA28/RESETN_11") (pintype "input"))
    )
    (net (code "72") (name "RX_D11") (class "Default")
      (node (ref "Q3") (pin "4") (pinfunction "S_4") (pintype "passive"))
      (node (ref "R15") (pin "1") (pinfunction "1_1") (pintype "passive"))
      (node (ref "U3") (pin "10") (pinfunction "PA23_10") (pintype "bidirectional"))
    )
    (net (code "73") (name "SWCLK") (class "Default")
      (node (ref "J2") (pin "2") (pinfunction "2_2") (pintype "passive"))
      (node (ref "R15") (pin "3") (pinfunction "1_3") (pintype "passive"))
      (node (ref "U3") (pin "12") (pinfunction "PA30/SWCLK_12") (pintype "bidirectional"))
    )
    (net (code "74") (name "SWDIO") (class "Default")
      (node (ref "J2") (pin "1") (pinfunction "1_1") (pintype "passive"))
      (node (ref "U3") (pin "13") (pinfunction "PA31/SWDIO_13") (pintype "bidirectional"))
    )
    (net (code "75") (name "TX_D11") (class "Default")
      (node (ref "Q3") (pin "1") (pinfunction "S_1") (pintype "passive"))
      (node (ref "R14") (pin "1") (pinfunction "1_1") (pintype "passive"))
      (node (ref "U3") (pin "9") (pinfunction "PA22_9") (pintype "bidirectional"))
    )
    (net (code "76") (name "UPDI") (class "Default")
      (node (ref "Q2") (pin "2") (pinfunction "S_2") (pintype "passive"))
      (node (ref "R15") (pin "4") (pinfunction "1_4") (pintype "passive"))
      (node (ref "U3") (pin "6") (pinfunction "PA14_6") (pintype "bidirectional"))
      (node (ref "U3") (pin "7") (pinfunction "PA15_7") (pintype "bidirectional"))
    )
    (net (code "77") (name "UPDI_5V") (class "Default")
      (node (ref "Q2") (pin "3") (pinfunction "D_3") (pintype "passive"))
      (node (ref "R4") (pin "1") (pinfunction "1_1") (pintype "passive"))
      (node (ref "U1") (pin "41") (pinfunction "UPDI_41") (pintype "bidirectional"))
    )
    (net (code "78") (name "V_USB") (class "Default")
      (node (ref "F1") (pin "1") (pinfunction "1_1") (pintype "bidirectional"))
      (node (ref "J1") (pin "A4B9") (pinfunction "VBUS_A4B9") (pintype "power_in"))
      (node (ref "J1") (pin "B4A9") (pinfunction "VBUS_B4A9") (pintype "power_in"))
      (node (ref "Z1") (pin "5") (pinfunction "VCC_5") (pintype "power_in"))
    )
    (net (code "79") (name "unconnected-(J1-SBU1-PadA8)") (class "Default")
      (node (ref "J1") (pin "A8") (pinfunction "SBU1_A8") (pintype "bidirectional"))
    )
    (net (code "80") (name "unconnected-(J1-SBU2-PadB8)") (class "Default")
      (node (ref "J1") (pin "B8") (pinfunction "SBU2_B8") (pintype "bidirectional"))
    )
    (net (code "81") (name "unconnected-(J4-Pad1)") (class "Default")
      (node (ref "J4") (pin "1") (pinfunction "1_1") (pintype "passive"))
    )
    (net (code "82") (name "unconnected-(J4-Pad2)") (class "Default")
      (node (ref "J4") (pin "2") (pinfunction "2_2") (pintype "passive"))
    )
    (net (code "83") (name "unconnected-(J5-Pad1)") (class "Default")
      (node (ref "J5") (pin "1") (pinfunction "1_1") (pintype "passive"))
    )
    (net (code "84") (name "unconnected-(U2-CLK-Pad20)") (class "Default")
      (node (ref "U2") (pin "20") (pinfunction "CLK_20") (pintype "bidirectional"))
    )
    (net (code "85") (name "unconnected-(U2-CMD-Pad19)") (class "Default")
      (node (ref "U2") (pin "19") (pinfunction "CMD_19") (pintype "bidirectional"))
    )
    (net (code "86") (name "unconnected-(U2-IO2-Pad24)") (class "Default")
      (node (ref "U2") (pin "24") (pinfunction "IO2_24") (pintype "bidirectional"))
    )
    (net (code "87") (name "unconnected-(U2-IO4-Pad26)") (class "Default")
      (node (ref "U2") (pin "26") (pinfunction "IO4_26") (pintype "bidirectional"))
    )
    (net (code "88") (name "unconnected-(U2-IO12-Pad14)") (class "Default")
      (node (ref "U2") (pin "14") (pinfunction "IO12_14") (pintype "bidirectional"))
    )
    (net (code "89") (name "unconnected-(U2-IO13-Pad16)") (class "Default")
      (node (ref "U2") (pin "16") (pinfunction "IO13_16") (pintype "bidirectional"))
    )
    (net (code "90") (name "unconnected-(U2-IO15-Pad23)") (class "Default")
      (node (ref "U2") (pin "23") (pinfunction "IO15_23") (pintype "bidirectional"))
    )
    (net (code "91") (name "unconnected-(U2-IO16-Pad27)") (class "Default")
      (node (ref "U2") (pin "27") (pinfunction "IO16_27") (pintype "bidirectional"))
    )
    (net (code "92") (name "unconnected-(U2-IO17-Pad28)") (class "Default")
      (node (ref "U2") (pin "28") (pinfunction "IO17_28") (pintype "bidirectional"))
    )
    (net (code "93") (name "unconnected-(U2-IO19-Pad31)") (class "Default")
      (node (ref "U2") (pin "31") (pinfunction "IO19_31") (pintype "bidirectional"))
    )
    (net (code "94") (name "unconnected-(U2-IO32-Pad8)") (class "Default")
      (node (ref "U2") (pin "8") (pinfunction "IO32_8") (pintype "bidirectional"))
    )
    (net (code "95") (name "unconnected-(U2-IO34-Pad6)") (class "Default")
      (node (ref "U2") (pin "6") (pinfunction "IO34_6") (pintype "bidirectional"))
    )
    (net (code "96") (name "unconnected-(U2-IO35-Pad7)") (class "Default")
      (node (ref "U2") (pin "7") (pinfunction "IO35_7") (pintype "bidirectional"))
    )
    (net (code "97") (name "unconnected-(U2-SD0-Pad21)") (class "Default")
      (node (ref "U2") (pin "21") (pinfunction "SD0_21") (pintype "bidirectional"))
    )
    (net (code "98") (name "unconnected-(U2-SD1-Pad22)") (class "Default")
      (node (ref "U2") (pin "22") (pinfunction "SD1_22") (pintype "bidirectional"))
    )
    (net (code "99") (name "unconnected-(U2-SD2-Pad17)") (class "Default")
      (node (ref "U2") (pin "17") (pinfunction "SD2_17") (pintype "bidirectional"))
    )
    (net (code "100") (name "unconnected-(U2-SD3-Pad18)") (class "Default")
      (node (ref "U2") (pin "18") (pinfunction "SD3_18") (pintype "bidirectional"))
    )
    (net (code "101") (name "unconnected-(U2-SVN-Pad5)") (class "Default")
      (node (ref "U2") (pin "5") (pinfunction "SVN_5") (pintype "bidirectional"))
    )
    (net (code "102") (name "unconnected-(U2-SVP-Pad4)") (class "Default")
      (node (ref "U2") (pin "4") (pinfunction "SVP_4") (pintype "bidirectional"))
    )
    (net (code "103") (name "unconnected-(U3-PA02-Pad18)") (class "Default")
      (node (ref "U3") (pin "18") (pinfunction "PA02_18") (pintype "bidirectional"))
    )
    (net (code "104") (name "unconnected-(U3-PA03-Pad19)") (class "Default")
      (node (ref "U3") (pin "19") (pinfunction "PA03_19") (pintype "bidirectional"))
    )
    (net (code "105") (name "unconnected-(U3-PA04-Pad20)") (class "Default")
      (node (ref "U3") (pin "20") (pinfunction "PA04_20") (pintype "bidirectional"))
    )
    (net (code "106") (name "unconnected-(U3-PA05-Pad1)") (class "Default")
      (node (ref "U3") (pin "1") (pinfunction "PA05_1") (pintype "bidirectional"))
    )
    (net (code "107") (name "unconnected-(U3-PA06-Pad2)") (class "Default")
      (node (ref "U3") (pin "2") (pinfunction "PA06_2") (pintype "bidirectional"))
    )
    (net (code "108") (name "unconnected-(U3-PA07-Pad3)") (class "Default")
      (node (ref "U3") (pin "3") (pinfunction "PA07_3") (pintype "bidirectional"))
    )
    (net (code "109") (name "unconnected-(U3-PA08{slash}XIN32-Pad4)") (class "Default")
      (node (ref "U3") (pin "4") (pinfunction "PA08/XIN32_4") (pintype "input"))
    )
    (net (code "110") (name "unconnected-(U3-PA09{slash}XOUT32-Pad5)") (class "Default")
      (node (ref "U3") (pin "5") (pinfunction "PA09/XOUT32_5") (pintype "input"))
    )
    (net (code "111") (name "unconnected-(U3-PA16-Pad8)") (class "Default")
      (node (ref "U3") (pin "8") (pinfunction "PA16_8") (pintype "bidirectional"))
    )
    (net (code "112") (name "unconnected-(U4-1A-Pad3)") (class "Default")
      (node (ref "U4") (pin "3") (pinfunction "1A_3") (pintype "bidirectional"))
    )
    (net (code "113") (name "unconnected-(U4-1Y-Pad2)") (class "Default")
      (node (ref "U4") (pin "2") (pinfunction "1Y_2") (pintype "bidirectional"))
    )
    (net (code "114") (name "unconnected-(Z1-IO3-Pad4)") (class "Default")
      (node (ref "Z1") (pin "4") (pinfunction "IO3_4") (pintype "passive"))
    )
    (net (code "115") (name "unconnected-(Z1-IO4-Pad6)") (class "Default")
      (node (ref "Z1") (pin "6") (pinfunction "IO4_6") (pintype "passive"))
    )
  )
)
